# 08-Connectors.net
KiCad netlist of a schematic drawn in Altium Designer
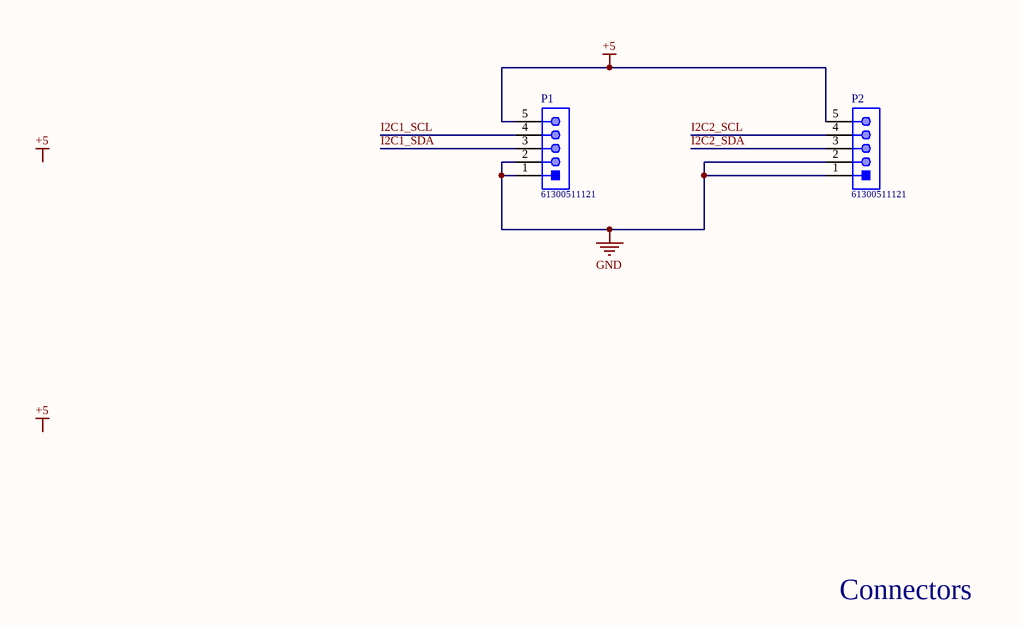
[diagram p0: 08-Connectors.SchDoc]

(export (version "E")
  (design (tool "Eeschema 10.0.6"))
  (components
    (comp (ref "P1")
      (value "61300511121")
      (footprint "61300511121")
      (description "THT Vertical Pin Header WR-PHD, Pitch 2.54 mm, Single Row, 5 pins")
      (fields (field (name "MANUFACTURER") "Wurth Elektronik") (field (name "PUBLISHER") "WurthElektronik"))
      (libsource (lib "Altium Content Vault") (part "WE-CN-1P-M-R5"))
    )
    (comp (ref "P2")
      (value "61300511121")
      (footprint "61300511121")
      (description "THT Vertical Pin Header WR-PHD, Pitch 2.54 mm, Single Row, 5 pins")
      (fields (field (name "MANUFACTURER") "Wurth Elektronik") (field (name "PUBLISHER") "WurthElektronik"))
      (libsource (lib "Altium Content Vault") (part "WE-CN-1P-M-R5"))
    )
  )
  (nets
    (net (code "1") (name "+5") (class "Default")
      (node (ref "P1") (pin "5") (pinfunction "5_5") (pintype "passive"))
      (node (ref "P2") (pin "5") (pinfunction "5_5") (pintype "passive"))
    )
    (net (code "2") (name "/I2C1_SCL") (class "Default")
      (node (ref "P1") (pin "4") (pinfunction "4_4") (pintype "passive"))
    )
    (net (code "3") (name "/I2C1_SDA") (class "Default")
      (node (ref "P1") (pin "3") (pinfunction "3_3") (pintype "passive"))
    )
    (net (code "4") (name "/I2C2_SCL") (class "Default")
      (node (ref "P2") (pin "4") (pinfunction "4_4") (pintype "passive"))
    )
    (net (code "5") (name "/I2C2_SDA") (class "Default")
      (node (ref "P2") (pin "3") (pinfunction "3_3") (pintype "passive"))
    )
    (net (code "6") (name "GND") (class "Default")
      (node (ref "P1") (pin "1") (pinfunction "1_1") (pintype "passive"))
      (node (ref "P1") (pin "2") (pinfunction "2_2") (pintype "passive"))
      (node (ref "P2") (pin "1") (pinfunction "1_1") (pintype "passive"))
      (node (ref "P2") (pin "2") (pinfunction "2_2") (pintype "passive"))
    )
  )
)
